# main_board.net
KiCad netlist of a schematic drawn in EAGLE
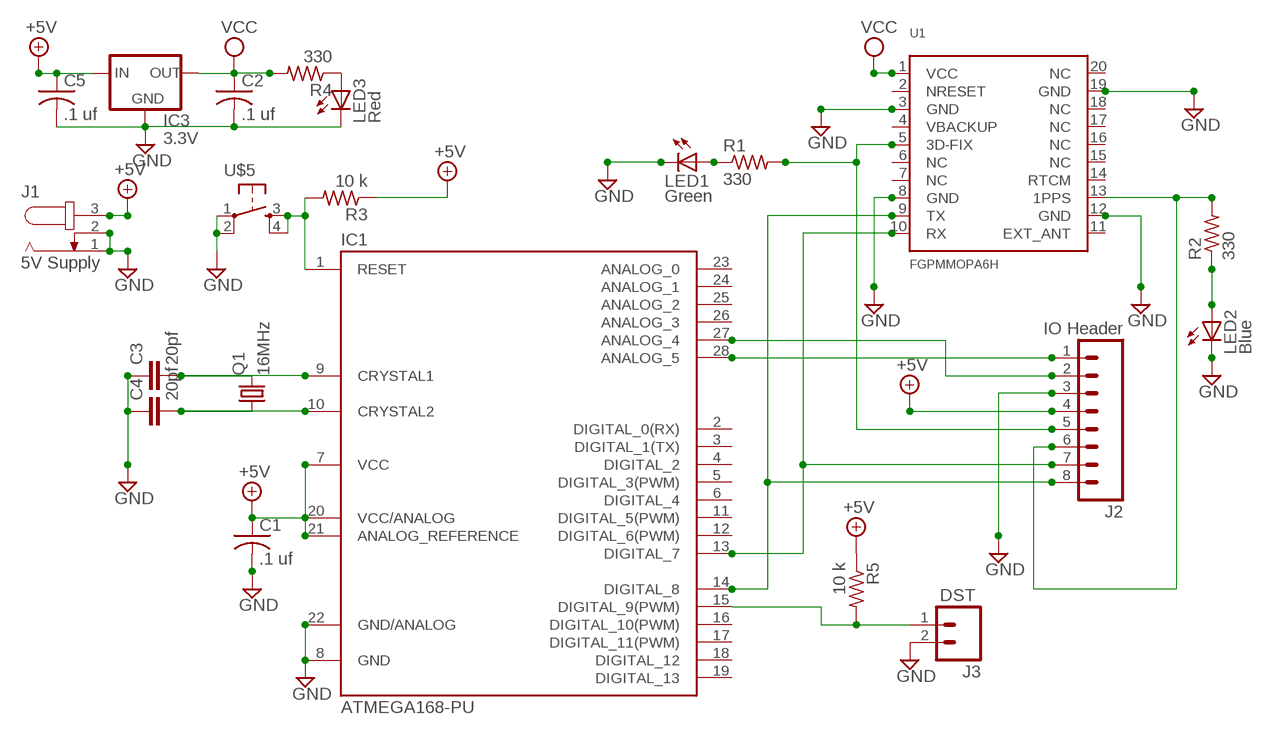
[diagram p0: schematic, sheet 1]

(export (version "E")
  (design (tool "Eeschema 10.0.6"))
  (components
    (comp (ref "C1")
      (value ".1 uf")
      (footprint "eagle-import:C025-025X050")
      (libsource (lib "eagle-import") (part "C-US025-025X050"))
    )
    (comp (ref "C2")
      (value ".1 uf")
      (footprint "eagle-import:C025-025X050")
      (libsource (lib "eagle-import") (part "C-US025-025X050"))
    )
    (comp (ref "C3")
      (value "20pf")
      (footprint "eagle-import:C025-024X044")
      (libsource (lib "eagle-import") (part "C-EU025-024X044"))
    )
    (comp (ref "C4")
      (value "20pf")
      (footprint "eagle-import:C025-024X044")
      (libsource (lib "eagle-import") (part "C-EU025-024X044"))
    )
    (comp (ref "C5")
      (value ".1 uf")
      (footprint "eagle-import:C025-025X050")
      (libsource (lib "eagle-import") (part "C-US025-025X050"))
    )
    (comp (ref "IC1")
      (value "ATMEGA168-PU")
      (footprint "eagle-import:DIL28-3")
      (libsource (lib "eagle-import") (part "ATMEGA168-PU"))
    )
    (comp (ref "IC3")
      (value "3.3V")
      (footprint "eagle-import:TO92")
      (libsource (lib "eagle-import") (part "MCP1700TRI"))
    )
    (comp (ref "J1")
      (value "5V Supply")
      (footprint "eagle-import:SPC4078")
      (libsource (lib "eagle-import") (part "JACK-PLUG1"))
    )
    (comp (ref "J2")
      (value "IO Header")
      (footprint "eagle-import:1X08_ROUND")
      (libsource (lib "eagle-import") (part "M08"))
    )
    (comp (ref "J3")
      (value "DST")
      (footprint "eagle-import:1X02_LOCK")
      (libsource (lib "eagle-import") (part "M02LOCK"))
    )
    (comp (ref "LED1")
      (value "Green")
      (footprint "eagle-import:LED3MM")
      (libsource (lib "eagle-import") (part "LED3MM"))
    )
    (comp (ref "LED2")
      (value "Blue")
      (footprint "eagle-import:LED3MM")
      (libsource (lib "eagle-import") (part "LED3MM"))
    )
    (comp (ref "LED3")
      (value "Red")
      (footprint "eagle-import:LED3MM")
      (libsource (lib "eagle-import") (part "LED3MM"))
    )
    (comp (ref "Q1")
      (value "16MHz")
      (footprint "eagle-import:HC18U-V")
      (libsource (lib "eagle-import") (part "CRYSTALHC18U-V"))
    )
    (comp (ref "R1")
      (value "330")
      (footprint "eagle-import:0204_5")
      (libsource (lib "eagle-import") (part "R-US_0204/5"))
    )
    (comp (ref "R2")
      (value "330")
      (footprint "eagle-import:0204_5")
      (libsource (lib "eagle-import") (part "R-US_0204/5"))
    )
    (comp (ref "R3")
      (value "10 k")
      (footprint "eagle-import:0204_5")
      (libsource (lib "eagle-import") (part "R-US_0204/5"))
    )
    (comp (ref "R4")
      (value "330")
      (footprint "eagle-import:0204_5")
      (libsource (lib "eagle-import") (part "R-US_0204/5"))
    )
    (comp (ref "R5")
      (value "10 k")
      (footprint "eagle-import:0204_5")
      (libsource (lib "eagle-import") (part "R-US_0204/5"))
    )
    (comp (ref "U$5")
      (value "TACTILE-SWITCH-PTH")
      (footprint "eagle-import:TAC-SWITCH-PTH")
      (libsource (lib "eagle-import") (part "TACTILE-SWITCH-PTH"))
    )
    (comp (ref "U1")
      (value "FGPMMOPA6H")
      (footprint "eagle-import:FGPMMOPA6H")
      (libsource (lib "eagle-import") (part "GPS_FGPMMOPA6H"))
    )
  )
  (nets
    (net (code "1") (name "+5V") (class "Default")
      (node (ref "C1") (pin "1") (pinfunction "1_1") (pintype "passive"))
      (node (ref "C5") (pin "1") (pinfunction "1_1") (pintype "passive"))
      (node (ref "IC1") (pin "20") (pinfunction "VCC/ANALOG_20") (pintype "passive"))
      (node (ref "IC1") (pin "21") (pinfunction "ANALOG_REFERENCE_21") (pintype "passive"))
      (node (ref "IC1") (pin "7") (pinfunction "VCC_7") (pintype "power_in"))
      (node (ref "IC3") (pin "2") (pinfunction "IN_2") (pintype "input"))
      (node (ref "J1") (pin "3") (pinfunction "3_3") (pintype "passive"))
      (node (ref "J2") (pin "4") (pinfunction "4_4") (pintype "passive"))
      (node (ref "R3") (pin "1") (pinfunction "1_1") (pintype "passive"))
      (node (ref "R5") (pin "1") (pinfunction "1_1") (pintype "passive"))
    )
    (net (code "2") (name "GND") (class "Default")
      (node (ref "C1") (pin "2") (pinfunction "2_2") (pintype "passive"))
      (node (ref "C2") (pin "2") (pinfunction "2_2") (pintype "passive"))
      (node (ref "C3") (pin "1") (pinfunction "1_1") (pintype "passive"))
      (node (ref "C4") (pin "1") (pinfunction "1_1") (pintype "passive"))
      (node (ref "C5") (pin "2") (pinfunction "2_2") (pintype "passive"))
      (node (ref "IC1") (pin "22") (pinfunction "GND/ANALOG_22") (pintype "power_in"))
      (node (ref "IC1") (pin "8") (pinfunction "GND_8") (pintype "power_in"))
      (node (ref "IC3") (pin "1") (pinfunction "GND_1") (pintype "input"))
      (node (ref "J1") (pin "1") (pinfunction "1_1") (pintype "passive"))
      (node (ref "J1") (pin "2") (pinfunction "2_2") (pintype "passive"))
      (node (ref "J2") (pin "3") (pinfunction "3_3") (pintype "passive"))
      (node (ref "J3") (pin "2") (pinfunction "2_2") (pintype "passive"))
      (node (ref "LED1") (pin "K") (pinfunction "C_K") (pintype "passive"))
      (node (ref "LED2") (pin "K") (pinfunction "C_K") (pintype "passive"))
      (node (ref "LED3") (pin "K") (pinfunction "C_K") (pintype "passive"))
      (node (ref "U$5") (pin "1") (pinfunction "1_1") (pintype "passive"))
      (node (ref "U$5") (pin "2") (pinfunction "2_2") (pintype "passive"))
      (node (ref "U1") (pin "12") (pinfunction "GND_12") (pintype "bidirectional"))
      (node (ref "U1") (pin "19") (pinfunction "GND_19") (pintype "bidirectional"))
      (node (ref "U1") (pin "3") (pinfunction "GND_3") (pintype "bidirectional"))
      (node (ref "U1") (pin "8") (pinfunction "GND_8") (pintype "bidirectional"))
    )
    (net (code "3") (name "Net-(IC1-ANALOG_4)") (class "Default")
      (node (ref "IC1") (pin "27") (pinfunction "ANALOG_4_27") (pintype "bidirectional"))
      (node (ref "J2") (pin "2") (pinfunction "2_2") (pintype "passive"))
    )
    (net (code "4") (name "Net-(IC1-ANALOG_5)") (class "Default")
      (node (ref "IC1") (pin "28") (pinfunction "ANALOG_5_28") (pintype "bidirectional"))
      (node (ref "J2") (pin "1") (pinfunction "1_1") (pintype "passive"))
    )
    (net (code "5") (name "Net-(IC1-CRYSTAL1)") (class "Default")
      (node (ref "C3") (pin "2") (pinfunction "2_2") (pintype "passive"))
      (node (ref "IC1") (pin "9") (pinfunction "CRYSTAL1_9") (pintype "bidirectional"))
      (node (ref "Q1") (pin "2") (pinfunction "2_2") (pintype "passive"))
    )
    (net (code "6") (name "Net-(IC1-CRYSTAL2)") (class "Default")
      (node (ref "C4") (pin "2") (pinfunction "2_2") (pintype "passive"))
      (node (ref "IC1") (pin "10") (pinfunction "CRYSTAL2_10") (pintype "bidirectional"))
      (node (ref "Q1") (pin "1") (pinfunction "1_1") (pintype "passive"))
    )
    (net (code "7") (name "Net-(IC1-DIGITAL_7)") (class "Default")
      (node (ref "IC1") (pin "13") (pinfunction "DIGITAL_7_13") (pintype "bidirectional"))
      (node (ref "J2") (pin "7") (pinfunction "7_7") (pintype "passive"))
      (node (ref "U1") (pin "10") (pinfunction "RX_10") (pintype "bidirectional"))
    )
    (net (code "8") (name "Net-(IC1-DIGITAL_8)") (class "Default")
      (node (ref "IC1") (pin "14") (pinfunction "DIGITAL_8_14") (pintype "bidirectional"))
      (node (ref "J2") (pin "8") (pinfunction "8_8") (pintype "passive"))
      (node (ref "U1") (pin "9") (pinfunction "TX_9") (pintype "bidirectional"))
    )
    (net (code "9") (name "Net-(IC1-DIGITAL_9(PWM))") (class "Default")
      (node (ref "IC1") (pin "15") (pinfunction "DIGITAL_9(PWM)_15") (pintype "bidirectional"))
      (node (ref "J3") (pin "1") (pinfunction "1_1") (pintype "passive"))
      (node (ref "R5") (pin "2") (pinfunction "2_2") (pintype "passive"))
    )
    (net (code "10") (name "Net-(IC1-RESET)") (class "Default")
      (node (ref "IC1") (pin "1") (pinfunction "RESET_1") (pintype "bidirectional"))
      (node (ref "R3") (pin "2") (pinfunction "2_2") (pintype "passive"))
      (node (ref "U$5") (pin "3") (pinfunction "3_3") (pintype "passive"))
      (node (ref "U$5") (pin "4") (pinfunction "4_4") (pintype "passive"))
    )
    (net (code "11") (name "Net-(LED1-PadA)") (class "Default")
      (node (ref "LED1") (pin "A") (pinfunction "A_A") (pintype "passive"))
      (node (ref "R1") (pin "1") (pinfunction "1_1") (pintype "passive"))
    )
    (net (code "12") (name "Net-(LED2-PadA)") (class "Default")
      (node (ref "LED2") (pin "A") (pinfunction "A_A") (pintype "passive"))
      (node (ref "R2") (pin "1") (pinfunction "1_1") (pintype "passive"))
    )
    (net (code "13") (name "Net-(LED3-PadA)") (class "Default")
      (node (ref "LED3") (pin "A") (pinfunction "A_A") (pintype "passive"))
      (node (ref "R4") (pin "1") (pinfunction "1_1") (pintype "passive"))
    )
    (net (code "14") (name "Net-(U1-1PPS)") (class "Default")
      (node (ref "J2") (pin "6") (pinfunction "6_6") (pintype "passive"))
      (node (ref "R2") (pin "2") (pinfunction "2_2") (pintype "passive"))
      (node (ref "U1") (pin "13") (pinfunction "1PPS_13") (pintype "bidirectional"))
    )
    (net (code "15") (name "Net-(U1-3D-FIX)") (class "Default")
      (node (ref "J2") (pin "5") (pinfunction "5_5") (pintype "passive"))
      (node (ref "R1") (pin "2") (pinfunction "2_2") (pintype "passive"))
      (node (ref "U1") (pin "5") (pinfunction "3D-FIX_5") (pintype "bidirectional"))
    )
    (net (code "16") (name "VCC") (class "Default")
      (node (ref "C2") (pin "1") (pinfunction "1_1") (pintype "passive"))
      (node (ref "IC3") (pin "3") (pinfunction "OUT_3") (pintype "passive"))
      (node (ref "R4") (pin "2") (pinfunction "2_2") (pintype "passive"))
      (node (ref "U1") (pin "1") (pinfunction "VCC_1") (pintype "bidirectional"))
    )
    (net (code "17") (name "unconnected-(IC1-ANALOG_0-Pad23)") (class "Default")
      (node (ref "IC1") (pin "23") (pinfunction "ANALOG_0_23") (pintype "bidirectional"))
    )
    (net (code "18") (name "unconnected-(IC1-ANALOG_1-Pad24)") (class "Default")
      (node (ref "IC1") (pin "24") (pinfunction "ANALOG_1_24") (pintype "bidirectional"))
    )
    (net (code "19") (name "unconnected-(IC1-ANALOG_2-Pad25)") (class "Default")
      (node (ref "IC1") (pin "25") (pinfunction "ANALOG_2_25") (pintype "bidirectional"))
    )
    (net (code "20") (name "unconnected-(IC1-ANALOG_3-Pad26)") (class "Default")
      (node (ref "IC1") (pin "26") (pinfunction "ANALOG_3_26") (pintype "bidirectional"))
    )
    (net (code "21") (name "unconnected-(IC1-DIGITAL_0(RX)-Pad2)") (class "Default")
      (node (ref "IC1") (pin "2") (pinfunction "DIGITAL_0(RX)_2") (pintype "bidirectional"))
    )
    (net (code "22") (name "unconnected-(IC1-DIGITAL_1(TX)-Pad3)") (class "Default")
      (node (ref "IC1") (pin "3") (pinfunction "DIGITAL_1(TX)_3") (pintype "bidirectional"))
    )
    (net (code "23") (name "unconnected-(IC1-DIGITAL_2-Pad4)") (class "Default")
      (node (ref "IC1") (pin "4") (pinfunction "DIGITAL_2_4") (pintype "bidirectional"))
    )
    (net (code "24") (name "unconnected-(IC1-DIGITAL_3(PWM)-Pad5)") (class "Default")
      (node (ref "IC1") (pin "5") (pinfunction "DIGITAL_3(PWM)_5") (pintype "bidirectional"))
    )
    (net (code "25") (name "unconnected-(IC1-DIGITAL_4-Pad6)") (class "Default")
      (node (ref "IC1") (pin "6") (pinfunction "DIGITAL_4_6") (pintype "bidirectional"))
    )
    (net (code "26") (name "unconnected-(IC1-DIGITAL_5(PWM)-Pad11)") (class "Default")
      (node (ref "IC1") (pin "11") (pinfunction "DIGITAL_5(PWM)_11") (pintype "bidirectional"))
    )
    (net (code "27") (name "unconnected-(IC1-DIGITAL_6(PWM)-Pad12)") (class "Default")
      (node (ref "IC1") (pin "12") (pinfunction "DIGITAL_6(PWM)_12") (pintype "bidirectional"))
    )
    (net (code "28") (name "unconnected-(IC1-DIGITAL_10(PWM)-Pad16)") (class "Default")
      (node (ref "IC1") (pin "16") (pinfunction "DIGITAL_10(PWM)_16") (pintype "bidirectional"))
    )
    (net (code "29") (name "unconnected-(IC1-DIGITAL_11(PWM)-Pad17)") (class "Default")
      (node (ref "IC1") (pin "17") (pinfunction "DIGITAL_11(PWM)_17") (pintype "bidirectional"))
    )
    (net (code "30") (name "unconnected-(IC1-DIGITAL_12-Pad18)") (class "Default")
      (node (ref "IC1") (pin "18") (pinfunction "DIGITAL_12_18") (pintype "bidirectional"))
    )
    (net (code "31") (name "unconnected-(IC1-DIGITAL_13-Pad19)") (class "Default")
      (node (ref "IC1") (pin "19") (pinfunction "DIGITAL_13_19") (pintype "bidirectional"))
    )
    (net (code "32") (name "unconnected-(U1-EXT_ANT-Pad11)") (class "Default")
      (node (ref "U1") (pin "11") (pinfunction "EXT_ANT_11") (pintype "bidirectional"))
    )
    (net (code "33") (name "unconnected-(U1-NC-Pad6)") (class "Default")
      (node (ref "U1") (pin "6") (pinfunction "NC_6") (pintype "bidirectional"))
    )
    (net (code "34") (name "unconnected-(U1-NC-Pad7)") (class "Default")
      (node (ref "U1") (pin "7") (pinfunction "NC_7") (pintype "bidirectional"))
    )
    (net (code "35") (name "unconnected-(U1-NC-Pad15)") (class "Default")
      (node (ref "U1") (pin "15") (pinfunction "NC_15") (pintype "bidirectional"))
    )
    (net (code "36") (name "unconnected-(U1-NC-Pad16)") (class "Default")
      (node (ref "U1") (pin "16") (pinfunction "NC_16") (pintype "bidirectional"))
    )
    (net (code "37") (name "unconnected-(U1-NC-Pad17)") (class "Default")
      (node (ref "U1") (pin "17") (pinfunction "NC_17") (pintype "bidirectional"))
    )
    (net (code "38") (name "unconnected-(U1-NC-Pad18)") (class "Default")
      (node (ref "U1") (pin "18") (pinfunction "NC_18") (pintype "bidirectional"))
    )
    (net (code "39") (name "unconnected-(U1-NC-Pad20)") (class "Default")
      (node (ref "U1") (pin "20") (pinfunction "NC_20") (pintype "bidirectional"))
    )
    (net (code "40") (name "unconnected-(U1-NRESET-Pad2)") (class "Default")
      (node (ref "U1") (pin "2") (pinfunction "NRESET_2") (pintype "bidirectional"))
    )
    (net (code "41") (name "unconnected-(U1-RTCM-Pad14)") (class "Default")
      (node (ref "U1") (pin "14") (pinfunction "RTCM_14") (pintype "bidirectional"))
    )
    (net (code "42") (name "unconnected-(U1-VBACKUP-Pad4)") (class "Default")
      (node (ref "U1") (pin "4") (pinfunction "VBACKUP_4") (pintype "bidirectional"))
    )
  )
)
